# side_small.net
KiCad netlist of a schematic drawn in EAGLE
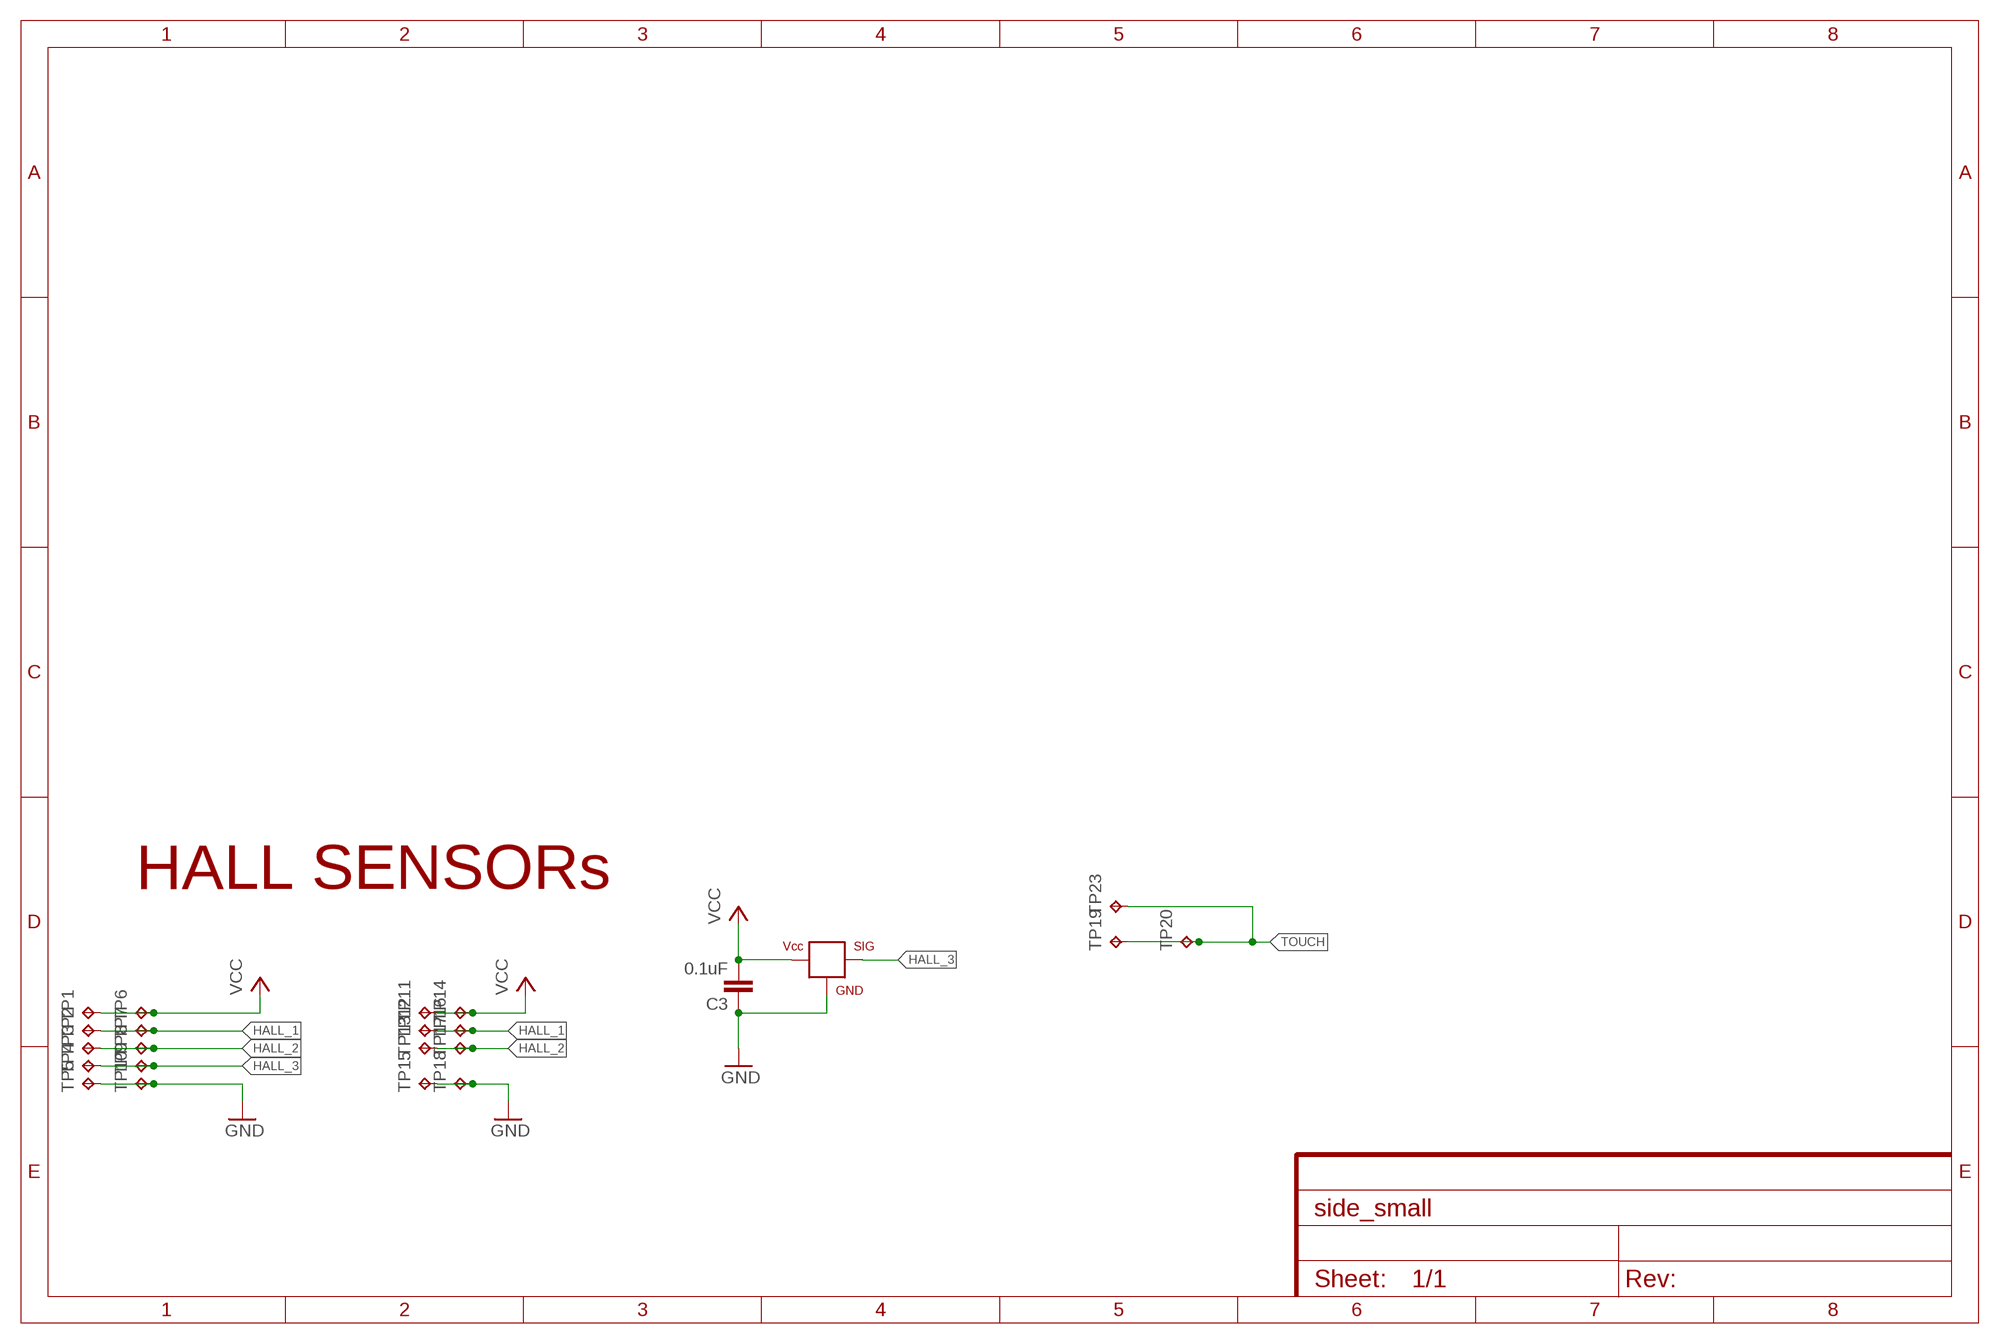
[diagram p0: schematic, sheet 1]

(export (version "E")
  (design (tool "Eeschema 10.0.6"))
  (components
    (comp (ref "C3")
      (value "0.1uF")
      (footprint "eagle-import:0603-CAP")
      (libsource (lib "eagle-import") (part "CAP0603-CAP"))
    )
    (comp (ref "HALL")
      (value "HALLEFFECT-A1326")
      (footprint "eagle-import:SOT23-3")
      (libsource (lib "eagle-import") (part "HALLEFFECT-A1326"))
    )
    (comp (ref "TP1")
      (value "TPTP10SQ")
      (footprint "eagle-import:TP10SQ")
      (libsource (lib "eagle-import") (part "TPTP10SQ"))
    )
    (comp (ref "TP2")
      (value "TPTP10SQ")
      (footprint "eagle-import:TP10SQ")
      (libsource (lib "eagle-import") (part "TPTP10SQ"))
    )
    (comp (ref "TP3")
      (value "TPTP10SQ")
      (footprint "eagle-import:TP10SQ")
      (libsource (lib "eagle-import") (part "TPTP10SQ"))
    )
    (comp (ref "TP4")
      (value "TPTP10SQ")
      (footprint "eagle-import:TP10SQ")
      (libsource (lib "eagle-import") (part "TPTP10SQ"))
    )
    (comp (ref "TP5")
      (value "TPTP10SQ")
      (footprint "eagle-import:TP10SQ")
      (libsource (lib "eagle-import") (part "TPTP10SQ"))
    )
    (comp (ref "TP6")
      (value "TPTP10SQ")
      (footprint "eagle-import:TP10SQ")
      (libsource (lib "eagle-import") (part "TPTP10SQ"))
    )
    (comp (ref "TP7")
      (value "TPTP10SQ")
      (footprint "eagle-import:TP10SQ")
      (libsource (lib "eagle-import") (part "TPTP10SQ"))
    )
    (comp (ref "TP8")
      (value "TPTP10SQ")
      (footprint "eagle-import:TP10SQ")
      (libsource (lib "eagle-import") (part "TPTP10SQ"))
    )
    (comp (ref "TP9")
      (value "TPTP10SQ")
      (footprint "eagle-import:TP10SQ")
      (libsource (lib "eagle-import") (part "TPTP10SQ"))
    )
    (comp (ref "TP10")
      (value "TPTP10SQ")
      (footprint "eagle-import:TP10SQ")
      (libsource (lib "eagle-import") (part "TPTP10SQ"))
    )
    (comp (ref "TP11")
      (value "TPTP10SQ")
      (footprint "eagle-import:TP10SQ")
      (libsource (lib "eagle-import") (part "TPTP10SQ"))
    )
    (comp (ref "TP12")
      (value "TPTP10SQ")
      (footprint "eagle-import:TP10SQ")
      (libsource (lib "eagle-import") (part "TPTP10SQ"))
    )
    (comp (ref "TP13")
      (value "TPTP10SQ")
      (footprint "eagle-import:TP10SQ")
      (libsource (lib "eagle-import") (part "TPTP10SQ"))
    )
    (comp (ref "TP14")
      (value "TPTP10SQ")
      (footprint "eagle-import:TP10SQ")
      (libsource (lib "eagle-import") (part "TPTP10SQ"))
    )
    (comp (ref "TP15")
      (value "TPTP10SQ")
      (footprint "eagle-import:TP10SQ")
      (libsource (lib "eagle-import") (part "TPTP10SQ"))
    )
    (comp (ref "TP16")
      (value "TPTP10SQ")
      (footprint "eagle-import:TP10SQ")
      (libsource (lib "eagle-import") (part "TPTP10SQ"))
    )
    (comp (ref "TP17")
      (value "TPTP10SQ")
      (footprint "eagle-import:TP10SQ")
      (libsource (lib "eagle-import") (part "TPTP10SQ"))
    )
    (comp (ref "TP18")
      (value "TPTP10SQ")
      (footprint "eagle-import:TP10SQ")
      (libsource (lib "eagle-import") (part "TPTP10SQ"))
    )
    (comp (ref "TP19")
      (value "TPTP10SQ")
      (footprint "eagle-import:TP10SQ")
      (libsource (lib "eagle-import") (part "TPTP10SQ"))
    )
    (comp (ref "TP20")
      (value "TPTP10SQ")
      (footprint "eagle-import:TP10SQ")
      (libsource (lib "eagle-import") (part "TPTP10SQ"))
    )
    (comp (ref "TP23")
      (value "TPTP10SQ")
      (footprint "eagle-import:TP10SQ")
      (libsource (lib "eagle-import") (part "TPTP10SQ"))
    )
  )
  (nets
    (net (code "1") (name "GND") (class "Default")
      (node (ref "C3") (pin "1") (pinfunction "1_1") (pintype "passive"))
      (node (ref "HALL") (pin "3") (pinfunction "GND_3") (pintype "bidirectional"))
      (node (ref "TP10") (pin "TP") (pinfunction "TP_TP") (pintype "input"))
      (node (ref "TP15") (pin "TP") (pinfunction "TP_TP") (pintype "input"))
      (node (ref "TP18") (pin "TP") (pinfunction "TP_TP") (pintype "input"))
      (node (ref "TP5") (pin "TP") (pinfunction "TP_TP") (pintype "input"))
    )
    (net (code "2") (name "HALL_1") (class "Default")
      (node (ref "TP12") (pin "TP") (pinfunction "TP_TP") (pintype "input"))
      (node (ref "TP16") (pin "TP") (pinfunction "TP_TP") (pintype "input"))
      (node (ref "TP2") (pin "TP") (pinfunction "TP_TP") (pintype "input"))
      (node (ref "TP7") (pin "TP") (pinfunction "TP_TP") (pintype "input"))
    )
    (net (code "3") (name "HALL_2") (class "Default")
      (node (ref "TP13") (pin "TP") (pinfunction "TP_TP") (pintype "input"))
      (node (ref "TP17") (pin "TP") (pinfunction "TP_TP") (pintype "input"))
      (node (ref "TP3") (pin "TP") (pinfunction "TP_TP") (pintype "input"))
      (node (ref "TP8") (pin "TP") (pinfunction "TP_TP") (pintype "input"))
    )
    (net (code "4") (name "HALL_3") (class "Default")
      (node (ref "HALL") (pin "2") (pinfunction "SIG_2") (pintype "bidirectional"))
      (node (ref "TP4") (pin "TP") (pinfunction "TP_TP") (pintype "input"))
      (node (ref "TP9") (pin "TP") (pinfunction "TP_TP") (pintype "input"))
    )
    (net (code "5") (name "TOUCH") (class "Default")
      (node (ref "TP19") (pin "TP") (pinfunction "TP_TP") (pintype "input"))
      (node (ref "TP20") (pin "TP") (pinfunction "TP_TP") (pintype "input"))
      (node (ref "TP23") (pin "TP") (pinfunction "TP_TP") (pintype "input"))
    )
    (net (code "6") (name "VCC") (class "Default")
      (node (ref "C3") (pin "2") (pinfunction "2_2") (pintype "passive"))
      (node (ref "HALL") (pin "1") (pinfunction "VCC_1") (pintype "bidirectional"))
      (node (ref "TP1") (pin "TP") (pinfunction "TP_TP") (pintype "input"))
      (node (ref "TP11") (pin "TP") (pinfunction "TP_TP") (pintype "input"))
      (node (ref "TP14") (pin "TP") (pinfunction "TP_TP") (pintype "input"))
      (node (ref "TP6") (pin "TP") (pinfunction "TP_TP") (pintype "input"))
    )
  )
)
